# controller_v3.net
KiCad netlist of a schematic drawn in EAGLE
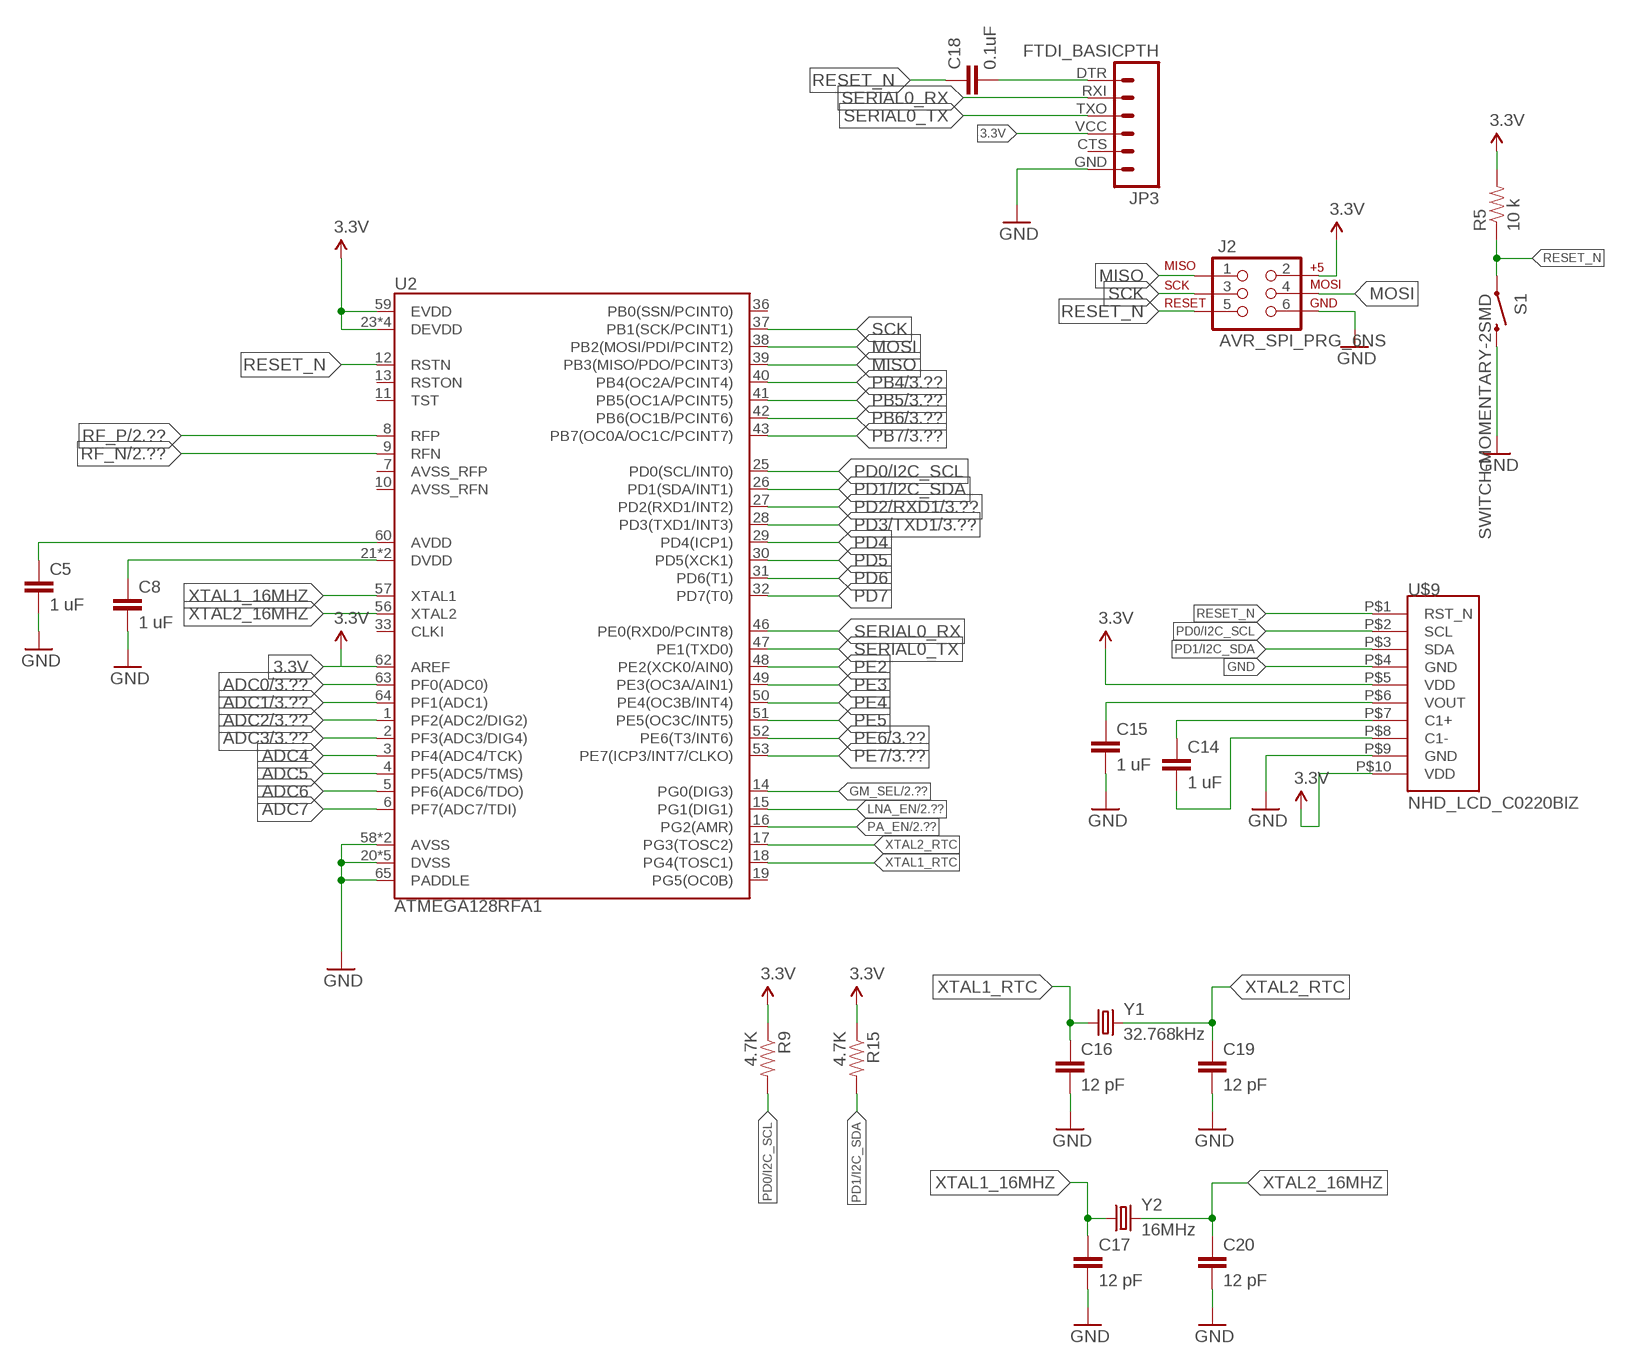
[diagram p0: schematic, sheet 1]
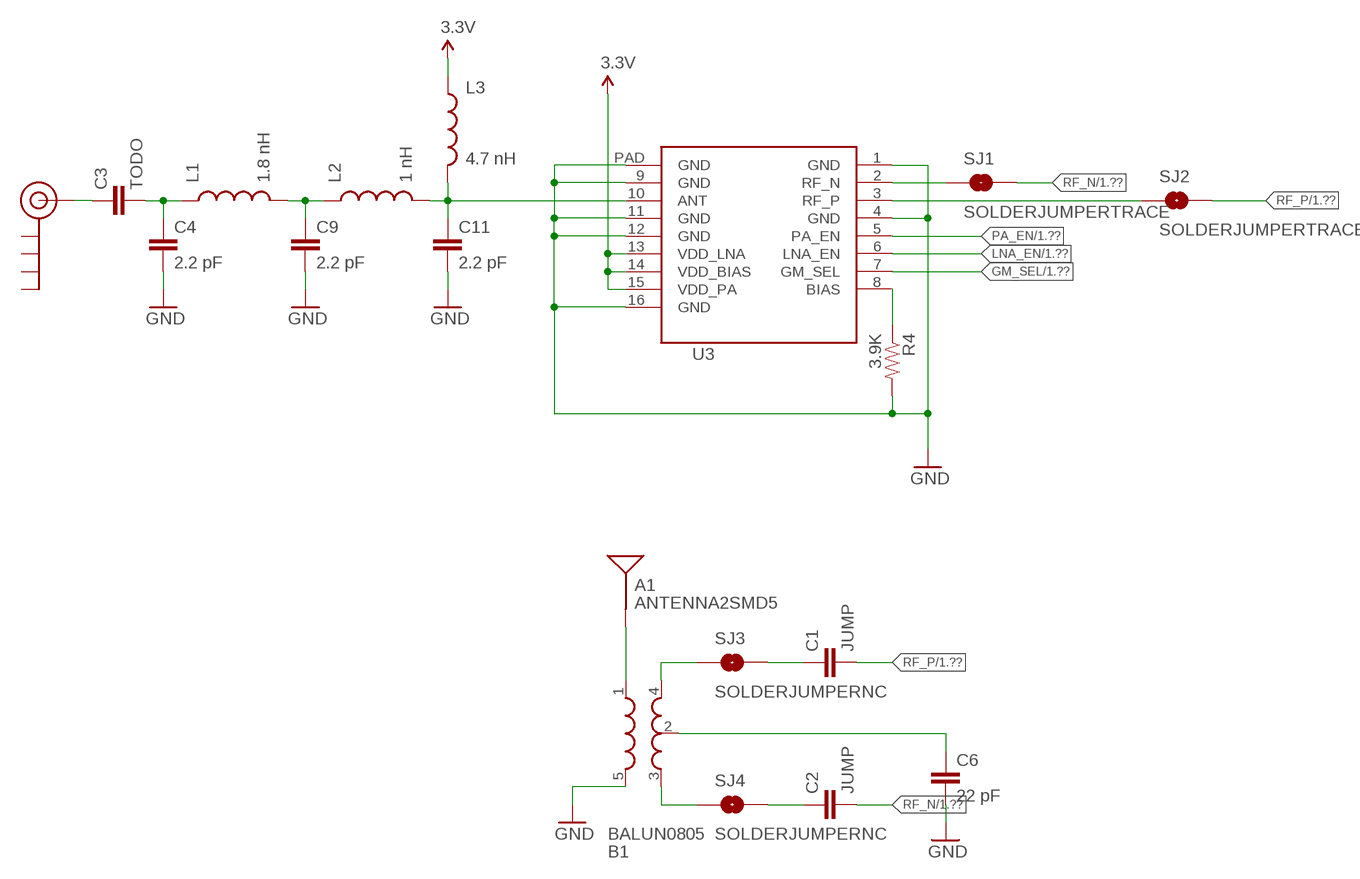
[diagram p1: schematic, sheet 2]
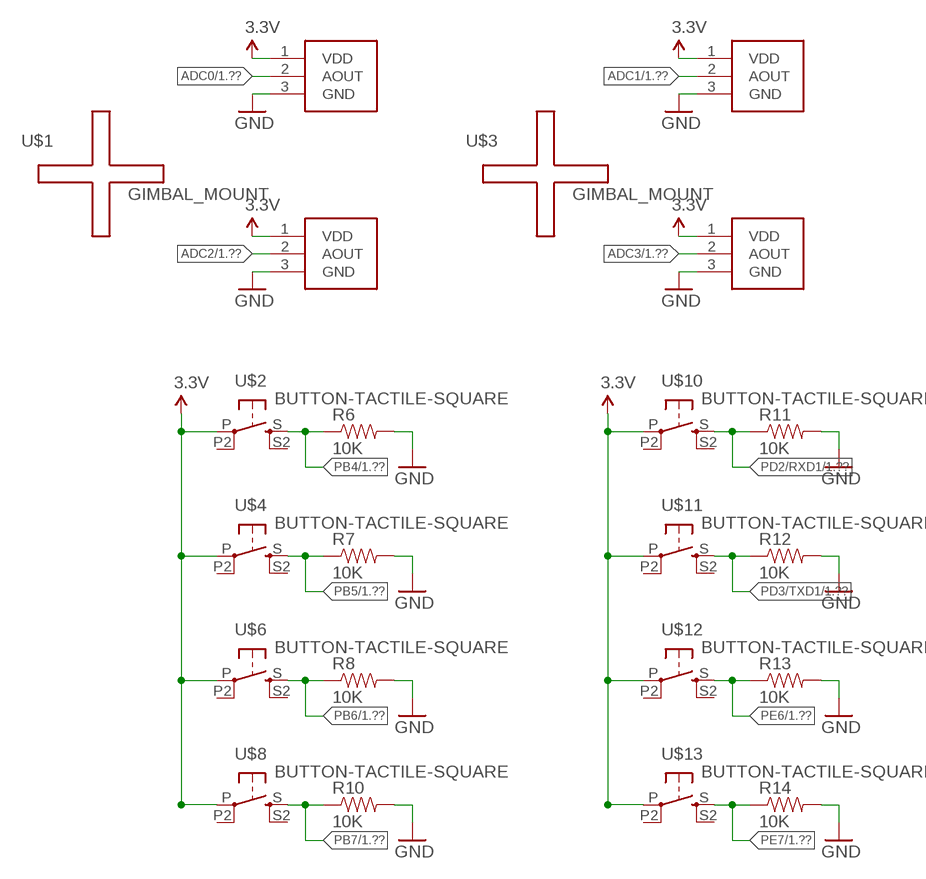
[diagram p2: schematic, sheet 3]
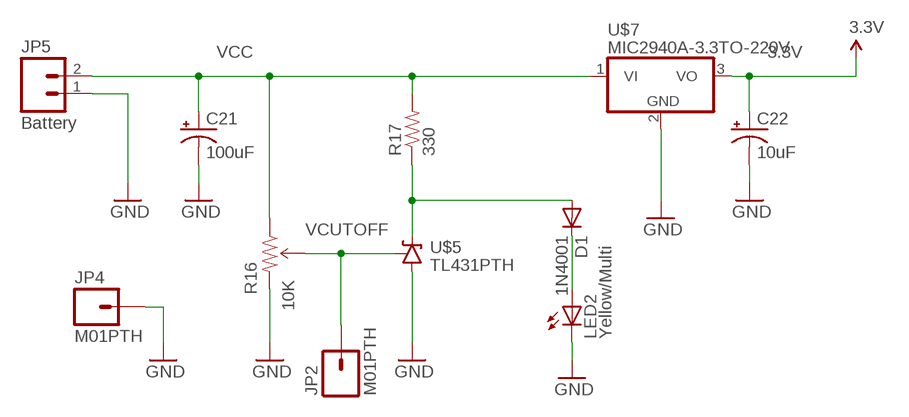
[diagram p3: schematic, sheet 4]

(export (version "E")
  (design (tool "Eeschema 10.0.6"))
  (components
    (comp (ref "J3")
      (value "GIMBAL_3PIN")
      (footprint "eagle-import:JST-3-PTH")
      (libsource (lib "eagle-import") (part "GIMBAL_3PIN"))
    )
    (comp (ref "J4")
      (value "GIMBAL_3PIN")
      (footprint "eagle-import:JST-3-PTH")
      (libsource (lib "eagle-import") (part "GIMBAL_3PIN"))
    )
    (comp (ref "J5")
      (value "GIMBAL_3PIN")
      (footprint "eagle-import:JST-3-PTH")
      (libsource (lib "eagle-import") (part "GIMBAL_3PIN"))
    )
    (comp (ref "J6")
      (value "GIMBAL_3PIN")
      (footprint "eagle-import:JST-3-PTH")
      (libsource (lib "eagle-import") (part "GIMBAL_3PIN"))
    )
    (comp (ref "R6")
      (value "10K")
      (footprint "eagle-import:0805")
      (libsource (lib "eagle-import") (part "RESISTOR0805-RES"))
    )
    (comp (ref "R7")
      (value "10K")
      (footprint "eagle-import:0805")
      (libsource (lib "eagle-import") (part "RESISTOR0805-RES"))
    )
    (comp (ref "R8")
      (value "10K")
      (footprint "eagle-import:0805")
      (libsource (lib "eagle-import") (part "RESISTOR0805-RES"))
    )
    (comp (ref "R10")
      (value "10K")
      (footprint "eagle-import:0805")
      (libsource (lib "eagle-import") (part "RESISTOR0805-RES"))
    )
    (comp (ref "R11")
      (value "10K")
      (footprint "eagle-import:0805")
      (libsource (lib "eagle-import") (part "RESISTOR0805-RES"))
    )
    (comp (ref "R12")
      (value "10K")
      (footprint "eagle-import:0805")
      (libsource (lib "eagle-import") (part "RESISTOR0805-RES"))
    )
    (comp (ref "R13")
      (value "10K")
      (footprint "eagle-import:0805")
      (libsource (lib "eagle-import") (part "RESISTOR0805-RES"))
    )
    (comp (ref "R14")
      (value "10K")
      (footprint "eagle-import:0805")
      (libsource (lib "eagle-import") (part "RESISTOR0805-RES"))
    )
    (comp (ref "U$1")
      (value "GIMBAL_MOUNT")
      (footprint "eagle-import:GIMBAL_FOOTPRINT")
      (libsource (lib "eagle-import") (part "GIMBAL_MOUNT"))
    )
    (comp (ref "U$2")
      (value "BUTTON-TACTILE-SQUARE")
      (footprint "eagle-import:BUTTON-TACTILE-SQUARE-ADAFRUIT1010")
      (libsource (lib "eagle-import") (part "BUTTON-TACTILE-SQUARE"))
    )
    (comp (ref "U$3")
      (value "GIMBAL_MOUNT")
      (footprint "eagle-import:GIMBAL_FOOTPRINT")
      (libsource (lib "eagle-import") (part "GIMBAL_MOUNT"))
    )
    (comp (ref "U$4")
      (value "BUTTON-TACTILE-SQUARE")
      (footprint "eagle-import:BUTTON-TACTILE-SQUARE-ADAFRUIT1010")
      (libsource (lib "eagle-import") (part "BUTTON-TACTILE-SQUARE"))
    )
    (comp (ref "U$6")
      (value "BUTTON-TACTILE-SQUARE")
      (footprint "eagle-import:BUTTON-TACTILE-SQUARE-ADAFRUIT1010")
      (libsource (lib "eagle-import") (part "BUTTON-TACTILE-SQUARE"))
    )
    (comp (ref "U$8")
      (value "BUTTON-TACTILE-SQUARE")
      (footprint "eagle-import:BUTTON-TACTILE-SQUARE-ADAFRUIT1010")
      (libsource (lib "eagle-import") (part "BUTTON-TACTILE-SQUARE"))
    )
    (comp (ref "U$10")
      (value "BUTTON-TACTILE-SQUARE")
      (footprint "eagle-import:BUTTON-TACTILE-SQUARE-ADAFRUIT1010")
      (libsource (lib "eagle-import") (part "BUTTON-TACTILE-SQUARE"))
    )
    (comp (ref "U$11")
      (value "BUTTON-TACTILE-SQUARE")
      (footprint "eagle-import:BUTTON-TACTILE-SQUARE-ADAFRUIT1010")
      (libsource (lib "eagle-import") (part "BUTTON-TACTILE-SQUARE"))
    )
    (comp (ref "U$12")
      (value "BUTTON-TACTILE-SQUARE")
      (footprint "eagle-import:BUTTON-TACTILE-SQUARE-ADAFRUIT1010")
      (libsource (lib "eagle-import") (part "BUTTON-TACTILE-SQUARE"))
    )
    (comp (ref "U$13")
      (value "BUTTON-TACTILE-SQUARE")
      (footprint "eagle-import:BUTTON-TACTILE-SQUARE-ADAFRUIT1010")
      (libsource (lib "eagle-import") (part "BUTTON-TACTILE-SQUARE"))
    )
    (comp (ref "C21")
      (value "100uF")
      (footprint "eagle-import:E3,5-8")
      (libsource (lib "eagle-import") (part "CPOL-USE3.5-8"))
    )
    (comp (ref "C22")
      (value "10uF")
      (footprint "eagle-import:E2,5-5")
      (libsource (lib "eagle-import") (part "CPOL-USE2.5-5"))
    )
    (comp (ref "D1")
      (value "1N4001")
      (footprint "eagle-import:DO41-10")
      (libsource (lib "eagle-import") (part "1N4004"))
    )
    (comp (ref "JP2")
      (value "M01PTH")
      (footprint "eagle-import:1X01")
      (libsource (lib "eagle-import") (part "M01PTH"))
    )
    (comp (ref "JP4")
      (value "M01PTH")
      (footprint "eagle-import:1X01")
      (libsource (lib "eagle-import") (part "M01PTH"))
    )
    (comp (ref "JP5")
      (value "Battery")
      (footprint "eagle-import:1X02")
      (libsource (lib "eagle-import") (part "M02PTH"))
    )
    (comp (ref "LED2")
      (value "Yellow/Multi")
      (footprint "eagle-import:LED5MM")
      (libsource (lib "eagle-import") (part "LED5MM"))
    )
    (comp (ref "R16")
      (value "10K")
      (footprint "eagle-import:3386U")
      (libsource (lib "eagle-import") (part "TRIMPOT-PTH-KNOB"))
    )
    (comp (ref "R17")
      (value "330")
      (footprint "eagle-import:AXIAL-0.3")
      (libsource (lib "eagle-import") (part "SparkFun_RESISTORAXIAL-0.3"))
    )
    (comp (ref "U$5")
      (value "TL431PTH")
      (footprint "eagle-import:TO-92")
      (libsource (lib "eagle-import") (part "TL431PTH"))
    )
    (comp (ref "U$7")
      (value "MIC2940A-3.3TO-220V")
      (footprint "eagle-import:TO-220V")
      (libsource (lib "eagle-import") (part "MIC2940A-3.3TO-220V"))
    )
    (comp (ref "C5")
      (value "1 uF")
      (footprint "eagle-import:0805")
      (libsource (lib "eagle-import") (part "CAP0805"))
    )
    (comp (ref "C8")
      (value "1 uF")
      (footprint "eagle-import:0805")
      (libsource (lib "eagle-import") (part "CAP0805"))
    )
    (comp (ref "C14")
      (value "1 uF")
      (footprint "eagle-import:0805")
      (libsource (lib "eagle-import") (part "CAP0805"))
    )
    (comp (ref "C15")
      (value "1 uF")
      (footprint "eagle-import:0805")
      (libsource (lib "eagle-import") (part "CAP0805"))
    )
    (comp (ref "C16")
      (value "12 pF")
      (footprint "eagle-import:0805")
      (libsource (lib "eagle-import") (part "CAP0805"))
    )
    (comp (ref "C17")
      (value "12 pF")
      (footprint "eagle-import:0805")
      (libsource (lib "eagle-import") (part "CAP0805"))
    )
    (comp (ref "C18")
      (value "0.1uF")
      (footprint "eagle-import:0805")
      (libsource (lib "eagle-import") (part "CAP0805"))
    )
    (comp (ref "C19")
      (value "12 pF")
      (footprint "eagle-import:0805")
      (libsource (lib "eagle-import") (part "CAP0805"))
    )
    (comp (ref "C20")
      (value "12 pF")
      (footprint "eagle-import:0805")
      (libsource (lib "eagle-import") (part "CAP0805"))
    )
    (comp (ref "J2")
      (value "AVR_SPI_PRG_6NS")
      (footprint "eagle-import:2X3-NS")
      (libsource (lib "eagle-import") (part "AVR_SPI_PRG_6NS"))
    )
    (comp (ref "JP3")
      (value "FTDI_BASICPTH")
      (footprint "eagle-import:FTDI_BASIC")
      (libsource (lib "eagle-import") (part "FTDI_BASICPTH"))
    )
    (comp (ref "R5")
      (value "10 k")
      (footprint "eagle-import:0805")
      (libsource (lib "eagle-import") (part "RESISTOR0805-RES"))
    )
    (comp (ref "R9")
      (value "4.7K")
      (footprint "eagle-import:0805")
      (libsource (lib "eagle-import") (part "RESISTOR0805-RES"))
    )
    (comp (ref "R15")
      (value "4.7K")
      (footprint "eagle-import:0805")
      (libsource (lib "eagle-import") (part "RESISTOR0805-RES"))
    )
    (comp (ref "S1")
      (value "SWITCH-MOMENTARY-2SMD")
      (footprint "eagle-import:TACTILE_SWITCH_SMD")
      (libsource (lib "eagle-import") (part "SWITCH-MOMENTARY-2SMD"))
    )
    (comp (ref "U$9")
      (value "NHD_LCD_C0220BIZ")
      (footprint "eagle-import:1X08-2MMPTH-LCD")
      (libsource (lib "eagle-import") (part "NHD_LCD_C0220BIZ"))
    )
    (comp (ref "U2")
      (value "ATMEGA128RFA1")
      (footprint "eagle-import:QFN-64")
      (libsource (lib "eagle-import") (part "ATMEGA128RFA1"))
    )
    (comp (ref "Y1")
      (value "32.768kHz")
      (footprint "eagle-import:CRYSTAL-32KHZ-SMD")
      (libsource (lib "eagle-import") (part "CRYSTAL32-SMD"))
    )
    (comp (ref "Y2")
      (value "16MHz")
      (footprint "eagle-import:CRYSTAL-SMD-5X3")
      (libsource (lib "eagle-import") (part "CRYSTAL5X3"))
    )
    (comp (ref "A1")
      (value "ANTENNA2SMD5")
      (footprint "eagle-import:ANTENNA-CHIP5")
      (libsource (lib "eagle-import") (part "ANTENNA2SMD5"))
    )
    (comp (ref "B1")
      (value "BALUN0805")
      (footprint "eagle-import:BALUN")
      (libsource (lib "eagle-import") (part "BALUN0805"))
    )
    (comp (ref "C1")
      (value "JUMP")
      (footprint "eagle-import:0805")
      (libsource (lib "eagle-import") (part "CAP0805"))
    )
    (comp (ref "C2")
      (value "JUMP")
      (footprint "eagle-import:0805")
      (libsource (lib "eagle-import") (part "CAP0805"))
    )
    (comp (ref "C3")
      (value "TODO")
      (footprint "eagle-import:0805")
      (libsource (lib "eagle-import") (part "CAP0805"))
    )
    (comp (ref "C4")
      (value "2.2 pF")
      (footprint "eagle-import:0805")
      (libsource (lib "eagle-import") (part "CAP0805"))
    )
    (comp (ref "C6")
      (value "22 pF")
      (footprint "eagle-import:0805")
      (libsource (lib "eagle-import") (part "CAP0805"))
    )
    (comp (ref "C9")
      (value "2.2 pF")
      (footprint "eagle-import:0805")
      (libsource (lib "eagle-import") (part "CAP0805"))
    )
    (comp (ref "C11")
      (value "2.2 pF")
      (footprint "eagle-import:0805")
      (libsource (lib "eagle-import") (part "CAP0805"))
    )
    (comp (ref "J$1")
      (value "SMA_EDGE")
      (footprint "eagle-import:SMA-EDGE")
      (libsource (lib "eagle-import") (part "SMA_EDGE"))
    )
    (comp (ref "L1")
      (value "1.8 nH")
      (footprint "eagle-import:0805")
      (libsource (lib "eagle-import") (part "INDUCTOR0805"))
    )
    (comp (ref "L2")
      (value "1 nH")
      (footprint "eagle-import:0805")
      (libsource (lib "eagle-import") (part "INDUCTOR0805"))
    )
    (comp (ref "L3")
      (value "4.7 nH")
      (footprint "eagle-import:0805")
      (libsource (lib "eagle-import") (part "INDUCTOR0805"))
    )
    (comp (ref "R4")
      (value "3.9K")
      (footprint "eagle-import:0805")
      (libsource (lib "eagle-import") (part "RESISTOR0805-RES"))
    )
    (comp (ref "SJ1")
      (value "SOLDERJUMPERTRACE")
      (footprint "eagle-import:SJ_2S-TRACE")
      (libsource (lib "eagle-import") (part "SOLDERJUMPERTRACE"))
    )
    (comp (ref "SJ2")
      (value "SOLDERJUMPERTRACE")
      (footprint "eagle-import:SJ_2S-TRACE")
      (libsource (lib "eagle-import") (part "SOLDERJUMPERTRACE"))
    )
    (comp (ref "SJ3")
      (value "SOLDERJUMPERNC")
      (footprint "eagle-import:SJ_2S")
      (libsource (lib "eagle-import") (part "SOLDERJUMPERNC"))
    )
    (comp (ref "SJ4")
      (value "SOLDERJUMPERNC")
      (footprint "eagle-import:SJ_2S")
      (libsource (lib "eagle-import") (part "SOLDERJUMPERNC"))
    )
    (comp (ref "U3")
      (value "RF_AMPLIFIER")
      (footprint "eagle-import:QFN65P400X400X100-17N")
      (libsource (lib "eagle-import") (part "CC2592QF"))
    )
  )
  (nets
    (net (code "1") (name "3.3V") (class "Default")
      (node (ref "C22") (pin "+") (pinfunction "+_+") (pintype "passive"))
      (node (ref "J2") (pin "2") (pinfunction "2_2") (pintype "passive"))
      (node (ref "J3") (pin "1") (pinfunction "VDD_1") (pintype "power_in"))
      (node (ref "J4") (pin "1") (pinfunction "VDD_1") (pintype "power_in"))
      (node (ref "J5") (pin "1") (pinfunction "VDD_1") (pintype "power_in"))
      (node (ref "J6") (pin "1") (pinfunction "VDD_1") (pintype "power_in"))
      (node (ref "JP3") (pin "VCC") (pinfunction "4_VCC") (pintype "passive"))
      (node (ref "L3") (pin "1") (pinfunction "1_1") (pintype "passive"))
      (node (ref "R15") (pin "1") (pinfunction "1_1") (pintype "passive"))
      (node (ref "R5") (pin "2") (pinfunction "2_2") (pintype "passive"))
      (node (ref "R9") (pin "1") (pinfunction "1_1") (pintype "passive"))
      (node (ref "U$10") (pin "P") (pinfunction "P_P") (pintype "passive"))
      (node (ref "U$11") (pin "P") (pinfunction "P_P") (pintype "passive"))
      (node (ref "U$12") (pin "P") (pinfunction "P_P") (pintype "passive"))
      (node (ref "U$13") (pin "P") (pinfunction "P_P") (pintype "passive"))
      (node (ref "U$2") (pin "P") (pinfunction "P_P") (pintype "passive"))
      (node (ref "U$4") (pin "P") (pinfunction "P_P") (pintype "passive"))
      (node (ref "U$6") (pin "P") (pinfunction "P_P") (pintype "passive"))
      (node (ref "U$7") (pin "3") (pinfunction "VO_3") (pintype "passive"))
      (node (ref "U$8") (pin "P") (pinfunction "P_P") (pintype "passive"))
      (node (ref "U$9") (pin "P$10") (pinfunction "VDD_P$10") (pintype "bidirectional"))
      (node (ref "U$9") (pin "P$5") (pinfunction "VDD_P$5") (pintype "bidirectional"))
      (node (ref "U2") (pin "23") (pinfunction "DEVDD_23") (pintype "bidirectional"))
      (node (ref "U2") (pin "34") (pinfunction "DEVDD_34") (pintype "bidirectional"))
      (node (ref "U2") (pin "44") (pinfunction "DEVDD_44") (pintype "bidirectional"))
      (node (ref "U2") (pin "54") (pinfunction "DEVDD_54") (pintype "bidirectional"))
      (node (ref "U2") (pin "59") (pinfunction "EVDD_59") (pintype "bidirectional"))
      (node (ref "U2") (pin "62") (pinfunction "AREF_62") (pintype "bidirectional"))
      (node (ref "U3") (pin "13") (pinfunction "VDD_LNA_13") (pintype "power_in"))
      (node (ref "U3") (pin "14") (pinfunction "VDD_BIAS_14") (pintype "power_in"))
      (node (ref "U3") (pin "15") (pinfunction "VDD_PA_15") (pintype "power_in"))
    )
    (net (code "2") (name "ADC0") (class "Default")
      (node (ref "J6") (pin "2") (pinfunction "AOUT_2") (pintype "bidirectional"))
      (node (ref "U2") (pin "63") (pinfunction "PF0(ADC0)_63") (pintype "bidirectional"))
    )
    (net (code "3") (name "ADC1") (class "Default")
      (node (ref "J3") (pin "2") (pinfunction "AOUT_2") (pintype "bidirectional"))
      (node (ref "U2") (pin "64") (pinfunction "PF1(ADC1)_64") (pintype "bidirectional"))
    )
    (net (code "4") (name "ADC2") (class "Default")
      (node (ref "J5") (pin "2") (pinfunction "AOUT_2") (pintype "bidirectional"))
      (node (ref "U2") (pin "1") (pinfunction "PF2(ADC2/DIG2)_1") (pintype "bidirectional"))
    )
    (net (code "5") (name "ADC3") (class "Default")
      (node (ref "J4") (pin "2") (pinfunction "AOUT_2") (pintype "bidirectional"))
      (node (ref "U2") (pin "2") (pinfunction "PF3(ADC3/DIG4)_2") (pintype "bidirectional"))
    )
    (net (code "6") (name "ADC4") (class "Default")
      (node (ref "U2") (pin "3") (pinfunction "PF4(ADC4/TCK)_3") (pintype "bidirectional"))
    )
    (net (code "7") (name "ADC5") (class "Default")
      (node (ref "U2") (pin "4") (pinfunction "PF5(ADC5/TMS)_4") (pintype "bidirectional"))
    )
    (net (code "8") (name "ADC6") (class "Default")
      (node (ref "U2") (pin "5") (pinfunction "PF6(ADC6/TDO)_5") (pintype "bidirectional"))
    )
    (net (code "9") (name "ADC7") (class "Default")
      (node (ref "U2") (pin "6") (pinfunction "PF7(ADC7/TDI)_6") (pintype "bidirectional"))
    )
    (net (code "10") (name "GM_SEL") (class "Default")
      (node (ref "U2") (pin "14") (pinfunction "PG0(DIG3)_14") (pintype "bidirectional"))
      (node (ref "U3") (pin "7") (pinfunction "GM_SEL_7") (pintype "input"))
    )
    (net (code "11") (name "GND") (class "Default")
      (node (ref "B1") (pin "5") (pinfunction "GND_5") (pintype "bidirectional"))
      (node (ref "C11") (pin "2") (pinfunction "2_2") (pintype "passive"))
      (node (ref "C15") (pin "2") (pinfunction "2_2") (pintype "passive"))
      (node (ref "C16") (pin "2") (pinfunction "2_2") (pintype "passive"))
      (node (ref "C17") (pin "2") (pinfunction "2_2") (pintype "passive"))
      (node (ref "C19") (pin "2") (pinfunction "2_2") (pintype "passive"))
      (node (ref "C20") (pin "2") (pinfunction "2_2") (pintype "passive"))
      (node (ref "C21") (pin "-") (pinfunction "-_-") (pintype "passive"))
      (node (ref "C22") (pin "-") (pinfunction "-_-") (pintype "passive"))
      (node (ref "C4") (pin "2") (pinfunction "2_2") (pintype "passive"))
      (node (ref "C5") (pin "2") (pinfunction "2_2") (pintype "passive"))
      (node (ref "C6") (pin "2") (pinfunction "2_2") (pintype "passive"))
      (node (ref "C8") (pin "2") (pinfunction "2_2") (pintype "passive"))
      (node (ref "C9") (pin "2") (pinfunction "2_2") (pintype "passive"))
      (node (ref "J2") (pin "6") (pinfunction "6_6") (pintype "passive"))
      (node (ref "J3") (pin "3") (pinfunction "GND_3") (pintype "power_in"))
      (node (ref "J4") (pin "3") (pinfunction "GND_3") (pintype "power_in"))
      (node (ref "J5") (pin "3") (pinfunction "GND_3") (pintype "power_in"))
      (node (ref "J6") (pin "3") (pinfunction "GND_3") (pintype "power_in"))
      (node (ref "JP3") (pin "GND") (pinfunction "6_GND") (pintype "passive"))
      (node (ref "JP4") (pin "1") (pinfunction "1_1") (pintype "passive"))
      (node (ref "JP5") (pin "1") (pinfunction "1_1") (pintype "passive"))
      (node (ref "LED2") (pin "K") (pinfunction "C_K") (pintype "passive"))
      (node (ref "R10") (pin "2") (pinfunction "2_2") (pintype "passive"))
      (node (ref "R11") (pin "2") (pinfunction "2_2") (pintype "passive"))
      (node (ref "R12") (pin "2") (pinfunction "2_2") (pintype "passive"))
      (node (ref "R13") (pin "2") (pinfunction "2_2") (pintype "passive"))
      (node (ref "R14") (pin "2") (pinfunction "2_2") (pintype "passive"))
      (node (ref "R16") (pin "3") (pinfunction "CW_3") (pintype "passive"))
      (node (ref "R4") (pin "2") (pinfunction "2_2") (pintype "passive"))
      (node (ref "R6") (pin "2") (pinfunction "2_2") (pintype "passive"))
      (node (ref "R7") (pin "2") (pinfunction "2_2") (pintype "passive"))
      (node (ref "R8") (pin "2") (pinfunction "2_2") (pintype "passive"))
      (node (ref "S1") (pin "3") (pinfunction "2_3") (pintype "passive"))
      (node (ref "U$5") (pin "2") (pinfunction "A_2") (pintype "passive"))
      (node (ref "U$7") (pin "2") (pinfunction "GND_2") (pintype "passive"))
      (node (ref "U$9") (pin "P$4") (pinfunction "GND_P$4") (pintype "bidirectional"))
      (node (ref "U$9") (pin "P$9") (pinfunction "GND_P$9") (pintype "bidirectional"))
      (node (ref "U2") (pin "20") (pinfunction "DVSS_20") (pintype "bidirectional"))
      (node (ref "U2") (pin "24") (pinfunction "DVSS_24") (pintype "bidirectional"))
      (node (ref "U2") (pin "35") (pinfunction "DVSS_35") (pintype "bidirectional"))
      (node (ref "U2") (pin "45") (pinfunction "DVSS_45") (pintype "bidirectional"))
      (node (ref "U2") (pin "55") (pinfunction "DVSS_55") (pintype "bidirectional"))
      (node (ref "U2") (pin "58") (pinfunction "AVSS_58") (pintype "bidirectional"))
      (node (ref "U2") (pin "61") (pinfunction "AVSS_61") (pintype "bidirectional"))
      (node (ref "U2") (pin "65") (pinfunction "PADDLE_65") (pintype "bidirectional"))
      (node (ref "U3") (pin "1") (pinfunction "GND_1") (pintype "power_in"))
      (node (ref "U3") (pin "11") (pinfunction "GND_11") (pintype "power_in"))
      (node (ref "U3") (pin "12") (pinfunction "GND_12") (pintype "power_in"))
      (node (ref "U3") (pin "16") (pinfunction "GND_16") (pintype "power_in"))
      (node (ref "U3") (pin "4") (pinfunction "GND_4") (pintype "power_in"))
      (node (ref "U3") (pin "9") (pinfunction "GND_9") (pintype "power_in"))
      (node (ref "U3") (pin "PAD") (pinfunction "GND_PAD") (pintype "power_in"))
    )
    (net (code "12") (name "LNA_EN") (class "Default")
      (node (ref "U2") (pin "15") (pinfunction "PG1(DIG1)_15") (pintype "bidirectional"))
      (node (ref "U3") (pin "6") (pinfunction "LNA_EN_6") (pintype "input"))
    )
    (net (code "13") (name "MISO") (class "Default")
      (node (ref "J2") (pin "1") (pinfunction "1_1") (pintype "passive"))
      (node (ref "U2") (pin "39") (pinfunction "PB3(MISO/PDO/PCINT3)_39") (pintype "bidirectional"))
    )
    (net (code "14") (name "MOSI") (class "Default")
      (node (ref "J2") (pin "4") (pinfunction "4_4") (pintype "passive"))
      (node (ref "U2") (pin "38") (pinfunction "PB2(MOSI/PDI/PCINT2)_38") (pintype "bidirectional"))
    )
    (net (code "15") (name "Net-(A1-SIGNAL)") (class "Default")
      (node (ref "A1") (pin "FEED") (pinfunction "SIGNAL_FEED") (pintype "bidirectional"))
      (node (ref "B1") (pin "1") (pinfunction "IN_1") (pintype "bidirectional"))
    )
    (net (code "16") (name "Net-(B1-GND-Pad2)") (class "Default")
      (node (ref "B1") (pin "2") (pinfunction "GND_2") (pintype "bidirectional"))
      (node (ref "C6") (pin "1") (pinfunction "1_1") (pintype "passive"))
    )
    (net (code "17") (name "Net-(B1-OUT1)") (class "Default")
      (node (ref "B1") (pin "4") (pinfunction "OUT1_4") (pintype "bidirectional"))
      (node (ref "SJ3") (pin "1") (pinfunction "1_1") (pintype "passive"))
    )
    (net (code "18") (name "Net-(B1-OUT2)") (class "Default")
      (node (ref "B1") (pin "3") (pinfunction "OUT2_3") (pintype "bidirectional"))
      (node (ref "SJ4") (pin "1") (pinfunction "1_1") (pintype "passive"))
    )
    (net (code "19") (name "Net-(C1-Pad1)") (class "Default")
      (node (ref "C1") (pin "1") (pinfunction "1_1") (pintype "passive"))
      (node (ref "SJ3") (pin "2") (pinfunction "2_2") (pintype "passive"))
    )
    (net (code "20") (name "Net-(C2-Pad1)") (class "Default")
      (node (ref "C2") (pin "1") (pinfunction "1_1") (pintype "passive"))
      (node (ref "SJ4") (pin "2") (pinfunction "2_2") (pintype "passive"))
    )
    (net (code "21") (name "Net-(C3-Pad2)") (class "Default")
      (node (ref "C3") (pin "2") (pinfunction "2_2") (pintype "passive"))
      (node (ref "C4") (pin "1") (pinfunction "1_1") (pintype "passive"))
      (node (ref "L1") (pin "1") (pinfunction "1_1") (pintype "passive"))
    )
    (net (code "22") (name "Net-(C8-Pad1)") (class "Default")
      (node (ref "C8") (pin "1") (pinfunction "1_1") (pintype "passive"))
      (node (ref "U2") (pin "21") (pinfunction "DVDD_21") (pintype "bidirectional"))
      (node (ref "U2") (pin "22") (pinfunction "DVDD_22") (pintype "bidirectional"))
    )
    (net (code "23") (name "Net-(C9-Pad1)") (class "Default")
      (node (ref "C9") (pin "1") (pinfunction "1_1") (pintype "passive"))
      (node (ref "L1") (pin "2") (pinfunction "2_2") (pintype "passive"))
      (node (ref "L2") (pin "1") (pinfunction "1_1") (pintype "passive"))
    )
    (net (code "24") (name "Net-(D1-PadC)") (class "Default")
      (node (ref "D1") (pin "C") (pinfunction "C_C") (pintype "passive"))
      (node (ref "LED2") (pin "A") (pinfunction "A_A") (pintype "passive"))
    )
    (net (code "25") (name "Net-(J$1-SIGNAL)") (class "Default")
      (node (ref "C3") (pin "1") (pinfunction "1_1") (pintype "passive"))
      (node (ref "J$1") (pin "SIG") (pinfunction "SIGNAL_SIG") (pintype "bidirectional"))
    )
    (net (code "26") (name "Net-(JP3-1)") (class "Default")
      (node (ref "C18") (pin "2") (pinfunction "2_2") (pintype "passive"))
      (node (ref "JP3") (pin "DTR") (pinfunction "1_DTR") (pintype "passive"))
    )
    (net (code "27") (name "Net-(R17-1)") (class "Default")
      (node (ref "D1") (pin "A") (pinfunction "A_A") (pintype "passive"))
      (node (ref "R17") (pin "P$1") (pinfunction "1_P$1") (pintype "passive"))
      (node (ref "U$5") (pin "3") (pinfunction "C_3") (pintype "passive"))
    )
    (net (code "28") (name "Net-(U$9-C1+)") (class "Default")
      (node (ref "C14") (pin "1") (pinfunction "1_1") (pintype "passive"))
      (node (ref "U$9") (pin "P$7") (pinfunction "C1+_P$7") (pintype "bidirectional"))
    )
    (net (code "29") (name "Net-(U$9-C1-)") (class "Default")
      (node (ref "C14") (pin "2") (pinfunction "2_2") (pintype "passive"))
      (node (ref "U$9") (pin "P$8") (pinfunction "C1-_P$8") (pintype "bidirectional"))
    )
    (net (code "30") (name "Net-(U$9-VOUT)") (class "Default")
      (node (ref "C15") (pin "1") (pinfunction "1_1") (pintype "passive"))
      (node (ref "U$9") (pin "P$6") (pinfunction "VOUT_P$6") (pintype "bidirectional"))
    )
    (net (code "31") (name "Net-(U2-AVDD)") (class "Default")
      (node (ref "C5") (pin "1") (pinfunction "1_1") (pintype "passive"))
      (node (ref "U2") (pin "60") (pinfunction "AVDD_60") (pintype "bidirectional"))
    )
    (net (code "32") (name "Net-(U3-ANT)") (class "Default")
      (node (ref "C11") (pin "1") (pinfunction "1_1") (pintype "passive"))
      (node (ref "L2") (pin "2") (pinfunction "2_2") (pintype "passive"))
      (node (ref "L3") (pin "2") (pinfunction "2_2") (pintype "passive"))
      (node (ref "U3") (pin "10") (pinfunction "ANT_10") (pintype "bidirectional"))
    )
    (net (code "33") (name "Net-(U3-BIAS)") (class "Default")
      (node (ref "R4") (pin "1") (pinfunction "1_1") (pintype "passive"))
      (node (ref "U3") (pin "8") (pinfunction "BIAS_8") (pintype "passive"))
    )
    (net (code "34") (name "Net-(U3-RF_N)") (class "Default")
      (node (ref "SJ1") (pin "1") (pinfunction "1_1") (pintype "passive"))
      (node (ref "U3") (pin "2") (pinfunction "RF_N_2") (pintype "bidirectional"))
    )
    (net (code "35") (name "Net-(U3-RF_P)") (class "Default")
      (node (ref "SJ2") (pin "1") (pinfunction "1_1") (pintype "passive"))
      (node (ref "U3") (pin "3") (pinfunction "RF_P_3") (pintype "bidirectional"))
    )
    (net (code "36") (name "PA_EN") (class "Default")
      (node (ref "U2") (pin "16") (pinfunction "PG2(AMR)_16") (pintype "bidirectional"))
      (node (ref "U3") (pin "5") (pinfunction "PA_EN_5") (pintype "input"))
    )
    (net (code "37") (name "PB4") (class "Default")
      (node (ref "R6") (pin "1") (pinfunction "1_1") (pintype "passive"))
      (node (ref "U$2") (pin "S") (pinfunction "S_S") (pintype "passive"))
      (node (ref "U2") (pin "40") (pinfunction "PB4(OC2A/PCINT4)_40") (pintype "bidirectional"))
    )
    (net (code "38") (name "PB5") (class "Default")
      (node (ref "R7") (pin "1") (pinfunction "1_1") (pintype "passive"))
      (node (ref "U$4") (pin "S") (pinfunction "S_S") (pintype "passive"))
      (node (ref "U2") (pin "41") (pinfunction "PB5(OC1A/PCINT5)_41") (pintype "bidirectional"))
    )
    (net (code "39") (name "PB6") (class "Default")
      (node (ref "R8") (pin "1") (pinfunction "1_1") (pintype "passive"))
      (node (ref "U$6") (pin "S") (pinfunction "S_S") (pintype "passive"))
      (node (ref "U2") (pin "42") (pinfunction "PB6(OC1B/PCINT6)_42") (pintype "bidirectional"))
    )
    (net (code "40") (name "PB7") (class "Default")
      (node (ref "R10") (pin "1") (pinfunction "1_1") (pintype "passive"))
      (node (ref "U$8") (pin "S") (pinfunction "S_S") (pintype "passive"))
      (node (ref "U2") (pin "43") (pinfunction "PB7(OC0A/OC1C/PCINT7)_43") (pintype "bidirectional"))
    )
    (net (code "41") (name "PD0{slash}I2C_SCL") (class "Default")
      (node (ref "R9") (pin "2") (pinfunction "2_2") (pintype "passive"))
      (node (ref "U$9") (pin "P$2") (pinfunction "SCL_P$2") (pintype "bidirectional"))
      (node (ref "U2") (pin "25") (pinfunction "PD0(SCL/INT0)_25") (pintype "bidirectional"))
    )
    (net (code "42") (name "PD1{slash}I2C_SDA") (class "Default")
      (node (ref "R15") (pin "2") (pinfunction "2_2") (pintype "passive"))
      (node (ref "U$9") (pin "P$3") (pinfunction "SDA_P$3") (pintype "bidirectional"))
      (node (ref "U2") (pin "26") (pinfunction "PD1(SDA/INT1)_26") (pintype "bidirectional"))
    )
    (net (code "43") (name "PD2{slash}RXD1") (class "Default")
      (node (ref "R11") (pin "1") (pinfunction "1_1") (pintype "passive"))
      (node (ref "U$10") (pin "S") (pinfunction "S_S") (pintype "passive"))
      (node (ref "U2") (pin "27") (pinfunction "PD2(RXD1/INT2)_27") (pintype "bidirectional"))
    )
    (net (code "44") (name "PD3{slash}TXD1") (class "Default")
      (node (ref "R12") (pin "1") (pinfunction "1_1") (pintype "passive"))
      (node (ref "U$11") (pin "S") (pinfunction "S_S") (pintype "passive"))
      (node (ref "U2") (pin "28") (pinfunction "PD3(TXD1/INT3)_28") (pintype "bidirectional"))
    )
    (net (code "45") (name "PD4") (class "Default")
      (node (ref "U2") (pin "29") (pinfunction "PD4(ICP1)_29") (pintype "bidirectional"))
    )
    (net (code "46") (name "PD5") (class "Default")
      (node (ref "U2") (pin "30") (pinfunction "PD5(XCK1)_30") (pintype "bidirectional"))
    )
    (net (code "47") (name "PD6") (class "Default")
      (node (ref "U2") (pin "31") (pinfunction "PD6(T1)_31") (pintype "bidirectional"))
    )
    (net (code "48") (name "PD7") (class "Default")
      (node (ref "U2") (pin "32") (pinfunction "PD7(T0)_32") (pintype "bidirectional"))
    )
    (net (code "49") (name "PE2") (class "Default")
      (node (ref "U2") (pin "48") (pinfunction "PE2(XCK0/AIN0)_48") (pintype "bidirectional"))
    )
    (net (code "50") (name "PE3") (class "Default")
      (node (ref "U2") (pin "49") (pinfunction "PE3(OC3A/AIN1)_49") (pintype "bidirectional"))
    )
    (net (code "51") (name "PE4") (class "Default")
      (node (ref "U2") (pin "50") (pinfunction "PE4(OC3B/INT4)_50") (pintype "bidirectional"))
    )
    (net (code "52") (name "PE5") (class "Default")
      (node (ref "U2") (pin "51") (pinfunction "PE5(OC3C/INT5)_51") (pintype "bidirectional"))
    )
    (net (code "53") (name "PE6") (class "Default")
      (node (ref "R13") (pin "1") (pinfunction "1_1") (pintype "passive"))
      (node (ref "U$12") (pin "S") (pinfunction "S_S") (pintype "passive"))
      (node (ref "U2") (pin "52") (pinfunction "PE6(T3/INT6)_52") (pintype "bidirectional"))
    )
    (net (code "54") (name "PE7") (class "Default")
      (node (ref "R14") (pin "1") (pinfunction "1_1") (pintype "passive"))
      (node (ref "U$13") (pin "S") (pinfunction "S_S") (pintype "passive"))
      (node (ref "U2") (pin "53") (pinfunction "PE7(ICP3/INT7/CLKO)_53") (pintype "bidirectional"))
    )
    (net (code "55") (name "RESET_N") (class "Default")
      (node (ref "C18") (pin "1") (pinfunction "1_1") (pintype "passive"))
      (node (ref "J2") (pin "5") (pinfunction "5_5") (pintype "passive"))
      (node (ref "R5") (pin "1") (pinfunction "1_1") (pintype "passive"))
      (node (ref "S1") (pin "1") (pinfunction "1_1") (pintype "passive"))
      (node (ref "U$9") (pin "P$1") (pinfunction "RST_N_P$1") (pintype "bidirectional"))
      (node (ref "U2") (pin "12") (pinfunction "RSTN_12") (pintype "bidirectional"))
    )
    (net (code "56") (name "RF_N") (class "Default")
      (node (ref "C2") (pin "2") (pinfunction "2_2") (pintype "passive"))
      (node (ref "SJ1") (pin "2") (pinfunction "2_2") (pintype "passive"))
      (node (ref "U2") (pin "9") (pinfunction "RFN_9") (pintype "bidirectional"))
    )
    (net (code "57") (name "RF_P") (class "Default")
      (node (ref "C1") (pin "2") (pinfunction "2_2") (pintype "passive"))
      (node (ref "SJ2") (pin "2") (pinfunction "2_2") (pintype "passive"))
      (node (ref "U2") (pin "8") (pinfunction "RFP_8") (pintype "bidirectional"))
    )
    (net (code "58") (name "SCK") (class "Default")
      (node (ref "J2") (pin "3") (pinfunction "3_3") (pintype "passive"))
      (node (ref "U2") (pin "37") (pinfunction "PB1(SCK/PCINT1)_37") (pintype "bidirectional"))
    )
    (net (code "59") (name "SERIAL0_RX") (class "Default")
      (node (ref "JP3") (pin "RXI") (pinfunction "2_RXI") (pintype "passive"))
      (node (ref "U2") (pin "46") (pinfunction "PE0(RXD0/PCINT8)_46") (pintype "bidirectional"))
    )
    (net (code "60") (name "SERIAL0_TX") (class "Default")
      (node (ref "JP3") (pin "TXO") (pinfunction "3_TXO") (pintype "passive"))
      (node (ref "U2") (pin "47") (pinfunction "PE1(TXD0)_47") (pintype "bidirectional"))
    )
    (net (code "61") (name "VCC") (class "Default")
      (node (ref "C21") (pin "+") (pinfunction "+_+") (pintype "passive"))
      (node (ref "JP5") (pin "2") (pinfunction "2_2") (pintype "passive"))
      (node (ref "R16") (pin "1") (pinfunction "CCW_1") (pintype "passive"))
      (node (ref "R17") (pin "P$2") (pinfunction "2_P$2") (pintype "passive"))
      (node (ref "U$7") (pin "1") (pinfunction "VI_1") (pintype "input"))
    )
    (net (code "62") (name "VCUTOFF") (class "Default")
      (node (ref "JP2") (pin "1") (pinfunction "1_1") (pintype "passive"))
      (node (ref "R16") (pin "2") (pinfunction "WIPER_2") (pintype "passive"))
      (node (ref "U$5") (pin "1") (pinfunction "R_1") (pintype "bidirectional"))
    )
    (net (code "63") (name "XTAL1_16MHZ") (class "Default")
      (node (ref "C17") (pin "1") (pinfunction "1_1") (pintype "passive"))
      (node (ref "U2") (pin "57") (pinfunction "XTAL1_57") (pintype "bidirectional"))
      (node (ref "Y2") (pin "1") (pinfunction "1_1") (pintype "passive"))
    )
    (net (code "64") (name "XTAL1_RTC") (class "Default")
      (node (ref "C16") (pin "1") (pinfunction "1_1") (pintype "passive"))
      (node (ref "U2") (pin "18") (pinfunction "PG4(TOSC1)_18") (pintype "bidirectional"))
      (node (ref "Y1") (pin "X1") (pinfunction "1_X1") (pintype "passive"))
    )
    (net (code "65") (name "XTAL2_16MHZ") (class "Default")
      (node (ref "C20") (pin "1") (pinfunction "1_1") (pintype "passive"))
      (node (ref "U2") (pin "56") (pinfunction "XTAL2_56") (pintype "bidirectional"))
      (node (ref "Y2") (pin "3") (pinfunction "2_3") (pintype "passive"))
    )
    (net (code "66") (name "XTAL2_RTC") (class "Default")
      (node (ref "C19") (pin "1") (pinfunction "1_1") (pintype "passive"))
      (node (ref "U2") (pin "17") (pinfunction "PG3(TOSC2)_17") (pintype "bidirectional"))
      (node (ref "Y1") (pin "X2") (pinfunction "2_X2") (pintype "passive"))
    )
    (net (code "67") (name "unconnected-(J$1-GND-PadGND@0)") (class "Default")
      (node (ref "J$1") (pin "GND@0") (pinfunction "GND_GND@0") (pintype "bidirectional"))
    )
    (net (code "68") (name "unconnected-(J$1-GND-PadGND@1)") (class "Default")
      (node (ref "J$1") (pin "GND@1") (pinfunction "GND_GND@1") (pintype "bidirectional"))
    )
    (net (code "69") (name "unconnected-(J$1-GND-PadGND@2)") (class "Default")
      (node (ref "J$1") (pin "GND@2") (pinfunction "GND_GND@2") (pintype "bidirectional"))
    )
    (net (code "70") (name "unconnected-(J$1-GND-PadGND@3)") (class "Default")
      (node (ref "J$1") (pin "GND@3") (pinfunction "GND_GND@3") (pintype "bidirectional"))
    )
    (net (code "71") (name "unconnected-(JP3-5-PadCTS)") (class "Default")
      (node (ref "JP3") (pin "CTS") (pinfunction "5_CTS") (pintype "passive"))
    )
    (net (code "72") (name "unconnected-(U$2-P1-PadP2)") (class "Default")
      (node (ref "U$2") (pin "P2") (pinfunction "P1_P2") (pintype "passive"))
    )
    (net (code "73") (name "unconnected-(U$2-S1-PadS2)") (class "Default")
      (node (ref "U$2") (pin "S2") (pinfunction "S1_S2") (pintype "passive"))
    )
    (net (code "74") (name "unconnected-(U$4-P1-PadP2)") (class "Default")
      (node (ref "U$4") (pin "P2") (pinfunction "P1_P2") (pintype "passive"))
    )
    (net (code "75") (name "unconnected-(U$4-S1-PadS2)") (class "Default")
      (node (ref "U$4") (pin "S2") (pinfunction "S1_S2") (pintype "passive"))
    )
    (net (code "76") (name "unconnected-(U$6-P1-PadP2)") (class "Default")
      (node (ref "U$6") (pin "P2") (pinfunction "P1_P2") (pintype "passive"))
    )
    (net (code "77") (name "unconnected-(U$6-S1-PadS2)") (class "Default")
      (node (ref "U$6") (pin "S2") (pinfunction "S1_S2") (pintype "passive"))
    )
    (net (code "78") (name "unconnected-(U$8-P1-PadP2)") (class "Default")
      (node (ref "U$8") (pin "P2") (pinfunction "P1_P2") (pintype "passive"))
    )
    (net (code "79") (name "unconnected-(U$8-S1-PadS2)") (class "Default")
      (node (ref "U$8") (pin "S2") (pinfunction "S1_S2") (pintype "passive"))
    )
    (net (code "80") (name "unconnected-(U$10-P1-PadP2)") (class "Default")
      (node (ref "U$10") (pin "P2") (pinfunction "P1_P2") (pintype "passive"))
    )
    (net (code "81") (name "unconnected-(U$10-S1-PadS2)") (class "Default")
      (node (ref "U$10") (pin "S2") (pinfunction "S1_S2") (pintype "passive"))
    )
    (net (code "82") (name "unconnected-(U$11-P1-PadP2)") (class "Default")
      (node (ref "U$11") (pin "P2") (pinfunction "P1_P2") (pintype "passive"))
    )
    (net (code "83") (name "unconnected-(U$11-S1-PadS2)") (class "Default")
      (node (ref "U$11") (pin "S2") (pinfunction "S1_S2") (pintype "passive"))
    )
    (net (code "84") (name "unconnected-(U$12-P1-PadP2)") (class "Default")
      (node (ref "U$12") (pin "P2") (pinfunction "P1_P2") (pintype "passive"))
    )
    (net (code "85") (name "unconnected-(U$12-S1-PadS2)") (class "Default")
      (node (ref "U$12") (pin "S2") (pinfunction "S1_S2") (pintype "passive"))
    )
    (net (code "86") (name "unconnected-(U$13-P1-PadP2)") (class "Default")
      (node (ref "U$13") (pin "P2") (pinfunction "P1_P2") (pintype "passive"))
    )
    (net (code "87") (name "unconnected-(U$13-S1-PadS2)") (class "Default")
      (node (ref "U$13") (pin "S2") (pinfunction "S1_S2") (pintype "passive"))
    )
    (net (code "88") (name "unconnected-(U2-AVSS_RFN-Pad10)") (class "Default")
      (node (ref "U2") (pin "10") (pinfunction "AVSS_RFN_10") (pintype "bidirectional"))
    )
    (net (code "89") (name "unconnected-(U2-AVSS_RFP-Pad7)") (class "Default")
      (node (ref "U2") (pin "7") (pinfunction "AVSS_RFP_7") (pintype "bidirectional"))
    )
    (net (code "90") (name "unconnected-(U2-CLKI-Pad33)") (class "Default")
      (node (ref "U2") (pin "33") (pinfunction "CLKI_33") (pintype "bidirectional"))
    )
    (net (code "91") (name "unconnected-(U2-PB0(SSN{slash}PCINT0)-Pad36)") (class "Default")
      (node (ref "U2") (pin "36") (pinfunction "PB0(SSN/PCINT0)_36") (pintype "bidirectional"))
    )
    (net (code "92") (name "unconnected-(U2-PG5(OC0B)-Pad19)") (class "Default")
      (node (ref "U2") (pin "19") (pinfunction "PG5(OC0B)_19") (pintype "bidirectional"))
    )
    (net (code "93") (name "unconnected-(U2-RSTON-Pad13)") (class "Default")
      (node (ref "U2") (pin "13") (pinfunction "RSTON_13") (pintype "bidirectional"))
    )
    (net (code "94") (name "unconnected-(U2-TST-Pad11)") (class "Default")
      (node (ref "U2") (pin "11") (pinfunction "TST_11") (pintype "bidirectional"))
    )
  )
)
